# NewMUM_route2.net
KiCad netlist of a schematic drawn in EAGLE
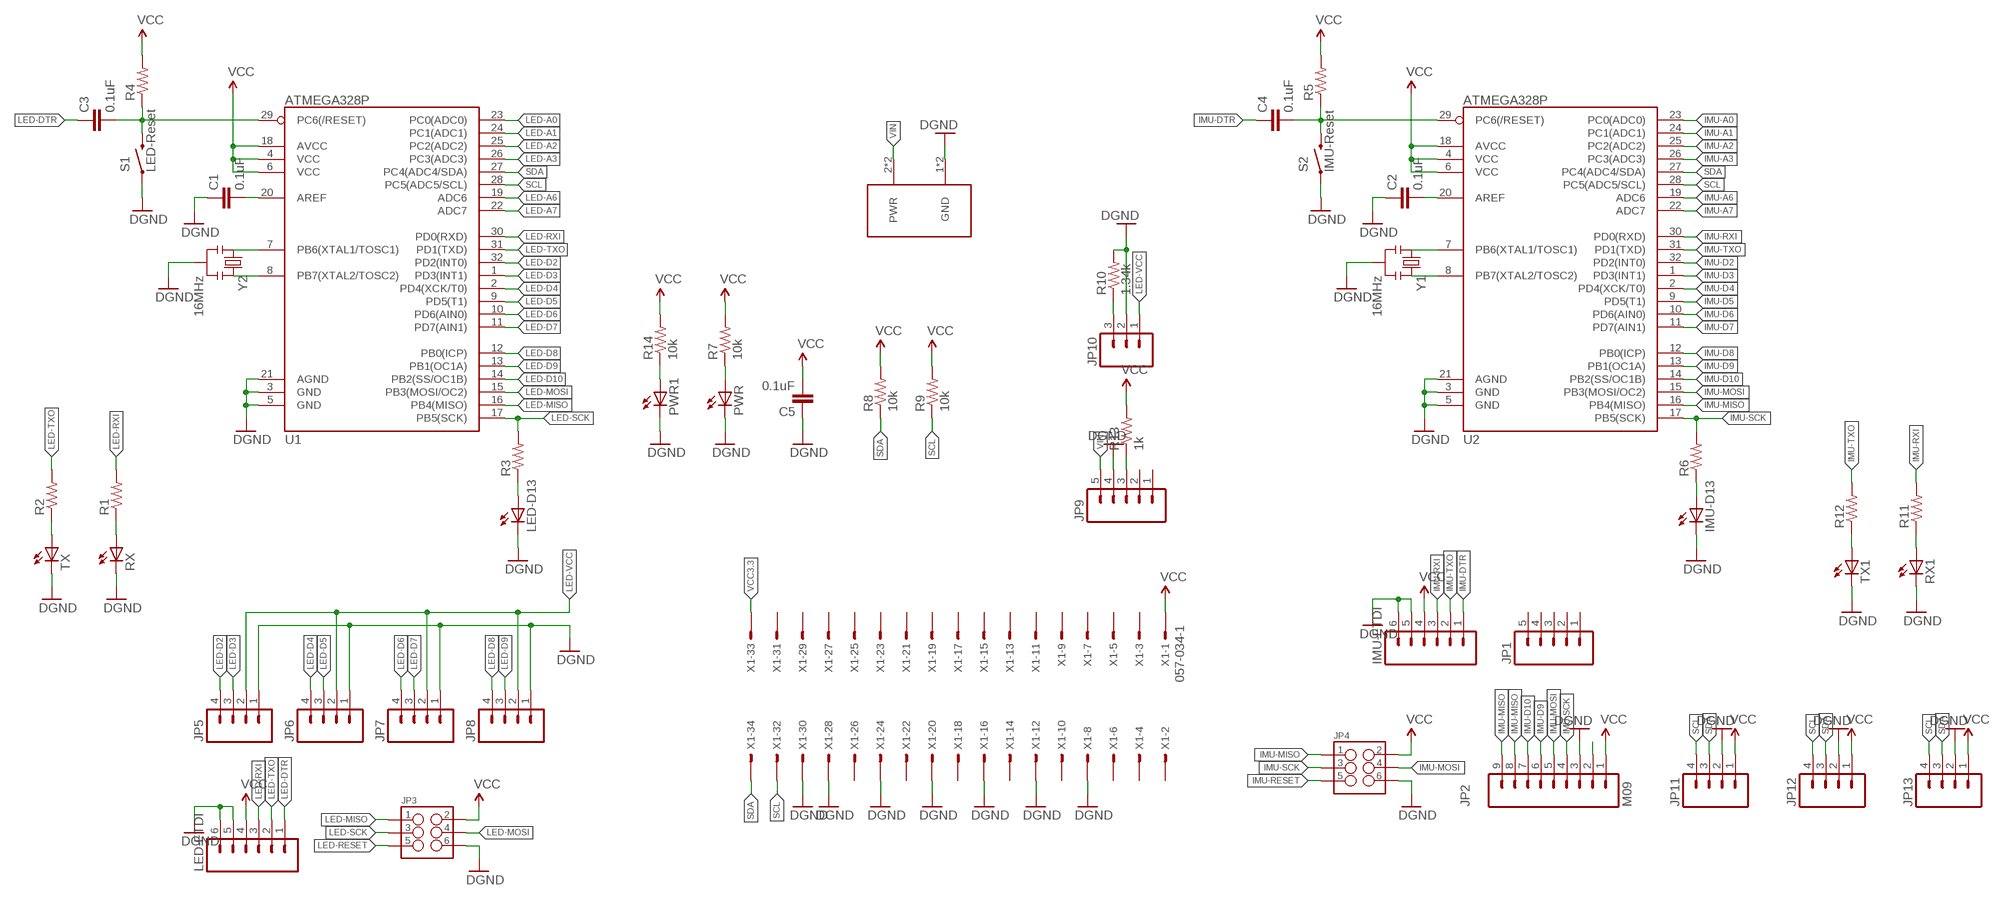
[diagram p0: schematic, sheet 1]

(export (version "E")
  (design (tool "Eeschema 10.0.6"))
  (components
    (comp (ref "C1")
      (value "0.1uF")
      (footprint "eagle-import:0805")
      (libsource (lib "eagle-import") (part "CAP0805"))
    )
    (comp (ref "C2")
      (value "0.1uF")
      (footprint "eagle-import:0805")
      (libsource (lib "eagle-import") (part "CAP0805"))
    )
    (comp (ref "C3")
      (value "0.1uF")
      (footprint "eagle-import:0805")
      (libsource (lib "eagle-import") (part "CAP0805"))
    )
    (comp (ref "C4")
      (value "0.1uF")
      (footprint "eagle-import:0805")
      (libsource (lib "eagle-import") (part "CAP0805"))
    )
    (comp (ref "C5")
      (value "0.1uF")
      (footprint "eagle-import:0805")
      (libsource (lib "eagle-import") (part "CAP0805"))
    )
    (comp (ref "IMU-D13")
      (value "LED1206")
      (footprint "eagle-import:LED-1206")
      (libsource (lib "eagle-import") (part "LED1206"))
    )
    (comp (ref "IMU-FTDI")
      (value "M06SIP")
      (footprint "eagle-import:1X06")
      (libsource (lib "eagle-import") (part "M06SIP"))
    )
    (comp (ref "JP1")
      (value "M05PTH")
      (footprint "eagle-import:1X05")
      (libsource (lib "eagle-import") (part "M05PTH"))
    )
    (comp (ref "JP2")
      (value "M09")
      (footprint "eagle-import:1X09")
      (libsource (lib "eagle-import") (part "M09"))
    )
    (comp (ref "JP3")
      (value "M03X22X3_SILK_SM")
      (footprint "eagle-import:2X3")
      (libsource (lib "eagle-import") (part "M03X22X3_SILK_SM"))
    )
    (comp (ref "JP4")
      (value "M03X22X3_SILK_SM")
      (footprint "eagle-import:2X3")
      (libsource (lib "eagle-import") (part "M03X22X3_SILK_SM"))
    )
    (comp (ref "JP5")
      (value "M04PTH")
      (footprint "eagle-import:1X04")
      (libsource (lib "eagle-import") (part "M04PTH"))
    )
    (comp (ref "JP6")
      (value "M04PTH")
      (footprint "eagle-import:1X04")
      (libsource (lib "eagle-import") (part "M04PTH"))
    )
    (comp (ref "JP7")
      (value "M04PTH")
      (footprint "eagle-import:1X04")
      (libsource (lib "eagle-import") (part "M04PTH"))
    )
    (comp (ref "JP8")
      (value "M04PTH")
      (footprint "eagle-import:1X04")
      (libsource (lib "eagle-import") (part "M04PTH"))
    )
    (comp (ref "JP9")
      (value "M05PTH")
      (footprint "eagle-import:1X05")
      (libsource (lib "eagle-import") (part "M05PTH"))
    )
    (comp (ref "JP10")
      (value "M03PTH")
      (footprint "eagle-import:1X03")
      (libsource (lib "eagle-import") (part "M03PTH"))
    )
    (comp (ref "JP11")
      (value "M04PTH")
      (footprint "eagle-import:1X04")
      (libsource (lib "eagle-import") (part "M04PTH"))
    )
    (comp (ref "JP12")
      (value "M04PTH")
      (footprint "eagle-import:1X04")
      (libsource (lib "eagle-import") (part "M04PTH"))
    )
    (comp (ref "JP13")
      (value "M04PTH")
      (footprint "eagle-import:1X04")
      (libsource (lib "eagle-import") (part "M04PTH"))
    )
    (comp (ref "LED-D13")
      (value "LED1206")
      (footprint "eagle-import:LED-1206")
      (libsource (lib "eagle-import") (part "LED1206"))
    )
    (comp (ref "LED-FTDI")
      (value "M06SIP")
      (footprint "eagle-import:1X06")
      (libsource (lib "eagle-import") (part "M06SIP"))
    )
    (comp (ref "PWR")
      (value "LED1206")
      (footprint "eagle-import:LED-1206")
      (libsource (lib "eagle-import") (part "LED1206"))
    )
    (comp (ref "PWR1")
      (value "LED1206")
      (footprint "eagle-import:LED-1206")
      (libsource (lib "eagle-import") (part "LED1206"))
    )
    (comp (ref "R1")
      (value "RESISTOR0805-RES")
      (footprint "eagle-import:0805")
      (libsource (lib "eagle-import") (part "RESISTOR0805-RES"))
    )
    (comp (ref "R2")
      (value "RESISTOR0805-RES")
      (footprint "eagle-import:0805")
      (libsource (lib "eagle-import") (part "RESISTOR0805-RES"))
    )
    (comp (ref "R3")
      (value "RESISTOR0805-RES")
      (footprint "eagle-import:0805")
      (libsource (lib "eagle-import") (part "RESISTOR0805-RES"))
    )
    (comp (ref "R4")
      (value "RESISTOR0805-RES")
      (footprint "eagle-import:0805")
      (libsource (lib "eagle-import") (part "RESISTOR0805-RES"))
    )
    (comp (ref "R5")
      (value "RESISTOR0805-RES")
      (footprint "eagle-import:0805")
      (libsource (lib "eagle-import") (part "RESISTOR0805-RES"))
    )
    (comp (ref "R6")
      (value "RESISTOR0805-RES")
      (footprint "eagle-import:0805")
      (libsource (lib "eagle-import") (part "RESISTOR0805-RES"))
    )
    (comp (ref "R7")
      (value "10k")
      (footprint "eagle-import:0805")
      (libsource (lib "eagle-import") (part "RESISTOR0805-RES"))
    )
    (comp (ref "R8")
      (value "10k")
      (footprint "eagle-import:0805")
      (libsource (lib "eagle-import") (part "RESISTOR0805-RES"))
    )
    (comp (ref "R9")
      (value "10k")
      (footprint "eagle-import:0805")
      (libsource (lib "eagle-import") (part "RESISTOR0805-RES"))
    )
    (comp (ref "R10")
      (value "1.34k")
      (footprint "eagle-import:AXIAL-0.3EZ")
      (libsource (lib "eagle-import") (part "RESISTOREZ"))
    )
    (comp (ref "R11")
      (value "RESISTOR0805-RES")
      (footprint "eagle-import:0805")
      (libsource (lib "eagle-import") (part "RESISTOR0805-RES"))
    )
    (comp (ref "R12")
      (value "RESISTOR0805-RES")
      (footprint "eagle-import:0805")
      (libsource (lib "eagle-import") (part "RESISTOR0805-RES"))
    )
    (comp (ref "R13")
      (value "1k")
      (footprint "eagle-import:0805")
      (libsource (lib "eagle-import") (part "RESISTOR0805-RES"))
    )
    (comp (ref "R14")
      (value "10k")
      (footprint "eagle-import:0805")
      (libsource (lib "eagle-import") (part "RESISTOR0805-RES"))
    )
    (comp (ref "RX")
      (value "LED1206")
      (footprint "eagle-import:LED-1206")
      (libsource (lib "eagle-import") (part "LED1206"))
    )
    (comp (ref "RX1")
      (value "LED1206")
      (footprint "eagle-import:LED-1206")
      (libsource (lib "eagle-import") (part "LED1206"))
    )
    (comp (ref "S1")
      (value "LED-Reset")
      (footprint "eagle-import:TACTILE-PTH")
      (libsource (lib "eagle-import") (part "SWITCH-MOMENTARY-2PTH"))
    )
    (comp (ref "S2")
      (value "IMU-Reset")
      (footprint "eagle-import:TACTILE-PTH")
      (libsource (lib "eagle-import") (part "SWITCH-MOMENTARY-2PTH"))
    )
    (comp (ref "TX")
      (value "LED1206")
      (footprint "eagle-import:LED-1206")
      (libsource (lib "eagle-import") (part "LED1206"))
    )
    (comp (ref "TX1")
      (value "LED1206")
      (footprint "eagle-import:LED-1206")
      (libsource (lib "eagle-import") (part "LED1206"))
    )
    (comp (ref "U$3")
      (value "LSF-SMT")
      (footprint "eagle-import:LSF-SMT")
      (libsource (lib "eagle-import") (part "LSF-SMT"))
    )
    (comp (ref "U1")
      (value "ATMEGA328P")
      (footprint "eagle-import:TQFP32-08")
      (libsource (lib "eagle-import") (part "ATMEGA328_SMT"))
    )
    (comp (ref "U2")
      (value "ATMEGA328P")
      (footprint "eagle-import:TQFP32-08")
      (libsource (lib "eagle-import") (part "ATMEGA328_SMT"))
    )
    (comp (ref "X1")
      (value "057-034-1")
      (footprint "eagle-import:057-034-1")
      (libsource (lib "eagle-import") (part "057-034-1"))
    )
    (comp (ref "Y1")
      (value "16MHz")
      (footprint "eagle-import:RESONATOR-SMD")
      (libsource (lib "eagle-import") (part "RESONATOR16MHZ"))
    )
    (comp (ref "Y2")
      (value "16MHz")
      (footprint "eagle-import:RESONATOR-SMD")
      (libsource (lib "eagle-import") (part "RESONATOR16MHZ"))
    )
  )
  (nets
    (net (code "1") (name "DGND") (class "Default")
      (node (ref "C1") (pin "1") (pinfunction "1_1") (pintype "passive"))
      (node (ref "C2") (pin "1") (pinfunction "1_1") (pintype "passive"))
      (node (ref "C5") (pin "1") (pinfunction "1_1") (pintype "passive"))
      (node (ref "IMU-D13") (pin "C") (pinfunction "C_C") (pintype "passive"))
      (node (ref "IMU-FTDI") (pin "5") (pinfunction "5_5") (pintype "passive"))
      (node (ref "IMU-FTDI") (pin "6") (pinfunction "6_6") (pintype "passive"))
      (node (ref "JP10") (pin "2") (pinfunction "2_2") (pintype "passive"))
      (node (ref "JP11") (pin "2") (pinfunction "2_2") (pintype "passive"))
      (node (ref "JP12") (pin "2") (pinfunction "2_2") (pintype "passive"))
      (node (ref "JP13") (pin "2") (pinfunction "2_2") (pintype "passive"))
      (node (ref "JP2") (pin "3") (pinfunction "3_3") (pintype "passive"))
      (node (ref "JP3") (pin "6") (pinfunction "6_6") (pintype "bidirectional"))
      (node (ref "JP4") (pin "6") (pinfunction "6_6") (pintype "bidirectional"))
      (node (ref "JP5") (pin "1") (pinfunction "1_1") (pintype "passive"))
      (node (ref "JP6") (pin "1") (pinfunction "1_1") (pintype "passive"))
      (node (ref "JP7") (pin "1") (pinfunction "1_1") (pintype "passive"))
      (node (ref "JP8") (pin "1") (pinfunction "1_1") (pintype "passive"))
      (node (ref "JP9") (pin "4") (pinfunction "4_4") (pintype "passive"))
      (node (ref "LED-D13") (pin "C") (pinfunction "C_C") (pintype "passive"))
      (node (ref "LED-FTDI") (pin "5") (pinfunction "5_5") (pintype "passive"))
      (node (ref "LED-FTDI") (pin "6") (pinfunction "6_6") (pintype "passive"))
      (node (ref "PWR") (pin "C") (pinfunction "C_C") (pintype "passive"))
      (node (ref "PWR1") (pin "C") (pinfunction "C_C") (pintype "passive"))
      (node (ref "R10") (pin "P$2") (pinfunction "2_P$2") (pintype "passive"))
      (node (ref "RX") (pin "C") (pinfunction "C_C") (pintype "passive"))
      (node (ref "RX1") (pin "C") (pinfunction "C_C") (pintype "passive"))
      (node (ref "S1") (pin "1") (pinfunction "1_1") (pintype "passive"))
      (node (ref "S2") (pin "1") (pinfunction "1_1") (pintype "passive"))
      (node (ref "TX") (pin "C") (pinfunction "C_C") (pintype "passive"))
      (node (ref "TX1") (pin "C") (pinfunction "C_C") (pintype "passive"))
      (node (ref "U$3") (pin "1") (pinfunction "GND_1") (pintype "bidirectional"))
      (node (ref "U$3") (pin "1-2") (pinfunction "GND_1-2") (pintype "bidirectional"))
      (node (ref "U1") (pin "21") (pinfunction "AGND_21") (pintype "bidirectional"))
      (node (ref "U1") (pin "3") (pinfunction "GND_3") (pintype "bidirectional"))
      (node (ref "U1") (pin "5") (pinfunction "GND_5") (pintype "bidirectional"))
      (node (ref "U2") (pin "21") (pinfunction "AGND_21") (pintype "bidirectional"))
      (node (ref "U2") (pin "3") (pinfunction "GND_3") (pintype "bidirectional"))
      (node (ref "U2") (pin "5") (pinfunction "GND_5") (pintype "bidirectional"))
      (node (ref "X1") (pin "12") (pinfunction "S_12") (pintype "passive"))
      (node (ref "X1") (pin "16") (pinfunction "S_16") (pintype "passive"))
      (node (ref "X1") (pin "20") (pinfunction "S_20") (pintype "passive"))
      (node (ref "X1") (pin "24") (pinfunction "S_24") (pintype "passive"))
      (node (ref "X1") (pin "28") (pinfunction "S_28") (pintype "passive"))
      (node (ref "X1") (pin "30") (pinfunction "S_30") (pintype "passive"))
      (node (ref "X1") (pin "8") (pinfunction "S_8") (pintype "passive"))
      (node (ref "Y1") (pin "2") (pinfunction "2_2") (pintype "passive"))
      (node (ref "Y2") (pin "2") (pinfunction "2_2") (pintype "passive"))
    )
    (net (code "2") (name "IMU-A0") (class "Default")
      (node (ref "U2") (pin "23") (pinfunction "PC0(ADC0)_23") (pintype "bidirectional"))
    )
    (net (code "3") (name "IMU-A1") (class "Default")
      (node (ref "U2") (pin "24") (pinfunction "PC1(ADC1)_24") (pintype "bidirectional"))
    )
    (net (code "4") (name "IMU-A2") (class "Default")
      (node (ref "U2") (pin "25") (pinfunction "PC2(ADC2)_25") (pintype "bidirectional"))
    )
    (net (code "5") (name "IMU-A3") (class "Default")
      (node (ref "U2") (pin "26") (pinfunction "PC3(ADC3)_26") (pintype "bidirectional"))
    )
    (net (code "6") (name "IMU-A6") (class "Default")
      (node (ref "U2") (pin "19") (pinfunction "ADC6_19") (pintype "bidirectional"))
    )
    (net (code "7") (name "IMU-A7") (class "Default")
      (node (ref "U2") (pin "22") (pinfunction "ADC7_22") (pintype "bidirectional"))
    )
    (net (code "8") (name "IMU-D2") (class "Default")
      (node (ref "U2") (pin "32") (pinfunction "PD2(INT0)_32") (pintype "bidirectional"))
    )
    (net (code "9") (name "IMU-D3") (class "Default")
      (node (ref "U2") (pin "1") (pinfunction "PD3(INT1)_1") (pintype "bidirectional"))
    )
    (net (code "10") (name "IMU-D4") (class "Default")
      (node (ref "U2") (pin "2") (pinfunction "PD4(XCK/T0)_2") (pintype "bidirectional"))
    )
    (net (code "11") (name "IMU-D5") (class "Default")
      (node (ref "U2") (pin "9") (pinfunction "PD5(T1)_9") (pintype "bidirectional"))
    )
    (net (code "12") (name "IMU-D6") (class "Default")
      (node (ref "U2") (pin "10") (pinfunction "PD6(AIN0)_10") (pintype "bidirectional"))
    )
    (net (code "13") (name "IMU-D7") (class "Default")
      (node (ref "U2") (pin "11") (pinfunction "PD7(AIN1)_11") (pintype "bidirectional"))
    )
    (net (code "14") (name "IMU-D8") (class "Default")
      (node (ref "U2") (pin "12") (pinfunction "PB0(ICP)_12") (pintype "bidirectional"))
    )
    (net (code "15") (name "IMU-D9") (class "Default")
      (node (ref "JP2") (pin "6") (pinfunction "6_6") (pintype "passive"))
      (node (ref "U2") (pin "13") (pinfunction "PB1(OC1A)_13") (pintype "bidirectional"))
    )
    (net (code "16") (name "IMU-D10") (class "Default")
      (node (ref "JP2") (pin "7") (pinfunction "7_7") (pintype "passive"))
      (node (ref "U2") (pin "14") (pinfunction "PB2(SS/OC1B)_14") (pintype "bidirectional"))
    )
    (net (code "17") (name "IMU-DTR") (class "Default")
      (node (ref "C4") (pin "1") (pinfunction "1_1") (pintype "passive"))
      (node (ref "IMU-FTDI") (pin "1") (pinfunction "1_1") (pintype "passive"))
    )
    (net (code "18") (name "IMU-MISO") (class "Default")
      (node (ref "JP2") (pin "8") (pinfunction "8_8") (pintype "passive"))
      (node (ref "JP2") (pin "9") (pinfunction "9_9") (pintype "passive"))
      (node (ref "JP4") (pin "1") (pinfunction "1_1") (pintype "bidirectional"))
      (node (ref "U2") (pin "16") (pinfunction "PB4(MISO)_16") (pintype "bidirectional"))
    )
    (net (code "19") (name "IMU-MOSI") (class "Default")
      (node (ref "JP2") (pin "5") (pinfunction "5_5") (pintype "passive"))
      (node (ref "JP4") (pin "4") (pinfunction "4_4") (pintype "bidirectional"))
      (node (ref "U2") (pin "15") (pinfunction "PB3(MOSI/OC2)_15") (pintype "bidirectional"))
    )
    (net (code "20") (name "IMU-RESET") (class "Default")
      (node (ref "C4") (pin "2") (pinfunction "2_2") (pintype "passive"))
      (node (ref "JP4") (pin "5") (pinfunction "5_5") (pintype "bidirectional"))
      (node (ref "R5") (pin "1") (pinfunction "1_1") (pintype "passive"))
      (node (ref "S2") (pin "3") (pinfunction "2_3") (pintype "passive"))
      (node (ref "U2") (pin "29") (pinfunction "PC6(/RESET)_29") (pintype "bidirectional"))
    )
    (net (code "21") (name "IMU-RXI") (class "Default")
      (node (ref "IMU-FTDI") (pin "3") (pinfunction "3_3") (pintype "passive"))
      (node (ref "R11") (pin "2") (pinfunction "2_2") (pintype "passive"))
      (node (ref "U2") (pin "30") (pinfunction "PD0(RXD)_30") (pintype "bidirectional"))
    )
    (net (code "22") (name "IMU-SCK") (class "Default")
      (node (ref "JP2") (pin "4") (pinfunction "4_4") (pintype "passive"))
      (node (ref "JP4") (pin "3") (pinfunction "3_3") (pintype "bidirectional"))
      (node (ref "R6") (pin "2") (pinfunction "2_2") (pintype "passive"))
      (node (ref "U2") (pin "17") (pinfunction "PB5(SCK)_17") (pintype "bidirectional"))
    )
    (net (code "23") (name "IMU-TXO") (class "Default")
      (node (ref "IMU-FTDI") (pin "2") (pinfunction "2_2") (pintype "passive"))
      (node (ref "R12") (pin "2") (pinfunction "2_2") (pintype "passive"))
      (node (ref "U2") (pin "31") (pinfunction "PD1(TXD)_31") (pintype "bidirectional"))
    )
    (net (code "24") (name "LED-A0") (class "Default")
      (node (ref "U1") (pin "23") (pinfunction "PC0(ADC0)_23") (pintype "bidirectional"))
    )
    (net (code "25") (name "LED-A1") (class "Default")
      (node (ref "U1") (pin "24") (pinfunction "PC1(ADC1)_24") (pintype "bidirectional"))
    )
    (net (code "26") (name "LED-A2") (class "Default")
      (node (ref "U1") (pin "25") (pinfunction "PC2(ADC2)_25") (pintype "bidirectional"))
    )
    (net (code "27") (name "LED-A3") (class "Default")
      (node (ref "U1") (pin "26") (pinfunction "PC3(ADC3)_26") (pintype "bidirectional"))
    )
    (net (code "28") (name "LED-A6") (class "Default")
      (node (ref "U1") (pin "19") (pinfunction "ADC6_19") (pintype "bidirectional"))
    )
    (net (code "29") (name "LED-A7") (class "Default")
      (node (ref "U1") (pin "22") (pinfunction "ADC7_22") (pintype "bidirectional"))
    )
    (net (code "30") (name "LED-D2") (class "Default")
      (node (ref "JP5") (pin "4") (pinfunction "4_4") (pintype "passive"))
      (node (ref "U1") (pin "32") (pinfunction "PD2(INT0)_32") (pintype "bidirectional"))
    )
    (net (code "31") (name "LED-D3") (class "Default")
      (node (ref "JP5") (pin "3") (pinfunction "3_3") (pintype "passive"))
      (node (ref "U1") (pin "1") (pinfunction "PD3(INT1)_1") (pintype "bidirectional"))
    )
    (net (code "32") (name "LED-D4") (class "Default")
      (node (ref "JP6") (pin "4") (pinfunction "4_4") (pintype "passive"))
      (node (ref "U1") (pin "2") (pinfunction "PD4(XCK/T0)_2") (pintype "bidirectional"))
    )
    (net (code "33") (name "LED-D5") (class "Default")
      (node (ref "JP6") (pin "3") (pinfunction "3_3") (pintype "passive"))
      (node (ref "U1") (pin "9") (pinfunction "PD5(T1)_9") (pintype "bidirectional"))
    )
    (net (code "34") (name "LED-D6") (class "Default")
      (node (ref "JP7") (pin "4") (pinfunction "4_4") (pintype "passive"))
      (node (ref "U1") (pin "10") (pinfunction "PD6(AIN0)_10") (pintype "bidirectional"))
    )
    (net (code "35") (name "LED-D7") (class "Default")
      (node (ref "JP7") (pin "3") (pinfunction "3_3") (pintype "passive"))
      (node (ref "U1") (pin "11") (pinfunction "PD7(AIN1)_11") (pintype "bidirectional"))
    )
    (net (code "36") (name "LED-D8") (class "Default")
      (node (ref "JP8") (pin "4") (pinfunction "4_4") (pintype "passive"))
      (node (ref "U1") (pin "12") (pinfunction "PB0(ICP)_12") (pintype "bidirectional"))
    )
    (net (code "37") (name "LED-D9") (class "Default")
      (node (ref "JP8") (pin "3") (pinfunction "3_3") (pintype "passive"))
      (node (ref "U1") (pin "13") (pinfunction "PB1(OC1A)_13") (pintype "bidirectional"))
    )
    (net (code "38") (name "LED-D10") (class "Default")
      (node (ref "U1") (pin "14") (pinfunction "PB2(SS/OC1B)_14") (pintype "bidirectional"))
    )
    (net (code "39") (name "LED-DTR") (class "Default")
      (node (ref "C3") (pin "1") (pinfunction "1_1") (pintype "passive"))
      (node (ref "LED-FTDI") (pin "1") (pinfunction "1_1") (pintype "passive"))
    )
    (net (code "40") (name "LED-MISO") (class "Default")
      (node (ref "JP3") (pin "1") (pinfunction "1_1") (pintype "bidirectional"))
      (node (ref "U1") (pin "16") (pinfunction "PB4(MISO)_16") (pintype "bidirectional"))
    )
    (net (code "41") (name "LED-MOSI") (class "Default")
      (node (ref "JP3") (pin "4") (pinfunction "4_4") (pintype "bidirectional"))
      (node (ref "U1") (pin "15") (pinfunction "PB3(MOSI/OC2)_15") (pintype "bidirectional"))
    )
    (net (code "42") (name "LED-RESET") (class "Default")
      (node (ref "C3") (pin "2") (pinfunction "2_2") (pintype "passive"))
      (node (ref "JP3") (pin "5") (pinfunction "5_5") (pintype "bidirectional"))
      (node (ref "R4") (pin "1") (pinfunction "1_1") (pintype "passive"))
      (node (ref "S1") (pin "3") (pinfunction "2_3") (pintype "passive"))
      (node (ref "U1") (pin "29") (pinfunction "PC6(/RESET)_29") (pintype "bidirectional"))
    )
    (net (code "43") (name "LED-RXI") (class "Default")
      (node (ref "LED-FTDI") (pin "3") (pinfunction "3_3") (pintype "passive"))
      (node (ref "R1") (pin "2") (pinfunction "2_2") (pintype "passive"))
      (node (ref "U1") (pin "30") (pinfunction "PD0(RXD)_30") (pintype "bidirectional"))
    )
    (net (code "44") (name "LED-SCK") (class "Default")
      (node (ref "JP3") (pin "3") (pinfunction "3_3") (pintype "bidirectional"))
      (node (ref "R3") (pin "2") (pinfunction "2_2") (pintype "passive"))
      (node (ref "U1") (pin "17") (pinfunction "PB5(SCK)_17") (pintype "bidirectional"))
    )
    (net (code "45") (name "LED-TXO") (class "Default")
      (node (ref "LED-FTDI") (pin "2") (pinfunction "2_2") (pintype "passive"))
      (node (ref "R2") (pin "2") (pinfunction "2_2") (pintype "passive"))
      (node (ref "U1") (pin "31") (pinfunction "PD1(TXD)_31") (pintype "bidirectional"))
    )
    (net (code "46") (name "LED-VCC") (class "Default")
      (node (ref "JP10") (pin "1") (pinfunction "1_1") (pintype "passive"))
      (node (ref "JP5") (pin "2") (pinfunction "2_2") (pintype "passive"))
      (node (ref "JP6") (pin "2") (pinfunction "2_2") (pintype "passive"))
      (node (ref "JP7") (pin "2") (pinfunction "2_2") (pintype "passive"))
      (node (ref "JP8") (pin "2") (pinfunction "2_2") (pintype "passive"))
    )
    (net (code "47") (name "Net-(IMU-D13-PadA)") (class "Default")
      (node (ref "IMU-D13") (pin "A") (pinfunction "A_A") (pintype "passive"))
      (node (ref "R6") (pin "1") (pinfunction "1_1") (pintype "passive"))
    )
    (net (code "48") (name "Net-(JP9-Pad3)") (class "Default")
      (node (ref "JP9") (pin "3") (pinfunction "3_3") (pintype "passive"))
      (node (ref "R13") (pin "1") (pinfunction "1_1") (pintype "passive"))
    )
    (net (code "49") (name "Net-(LED-D13-PadA)") (class "Default")
      (node (ref "LED-D13") (pin "A") (pinfunction "A_A") (pintype "passive"))
      (node (ref "R3") (pin "1") (pinfunction "1_1") (pintype "passive"))
    )
    (net (code "50") (name "Net-(PWR-PadA)") (class "Default")
      (node (ref "PWR") (pin "A") (pinfunction "A_A") (pintype "passive"))
      (node (ref "R7") (pin "1") (pinfunction "1_1") (pintype "passive"))
    )
    (net (code "51") (name "Net-(PWR1-PadA)") (class "Default")
      (node (ref "PWR1") (pin "A") (pinfunction "A_A") (pintype "passive"))
      (node (ref "R14") (pin "1") (pinfunction "1_1") (pintype "passive"))
    )
    (net (code "52") (name "Net-(R1-Pad1)") (class "Default")
      (node (ref "R1") (pin "1") (pinfunction "1_1") (pintype "passive"))
      (node (ref "RX") (pin "A") (pinfunction "A_A") (pintype "passive"))
    )
    (net (code "53") (name "Net-(R2-Pad1)") (class "Default")
      (node (ref "R2") (pin "1") (pinfunction "1_1") (pintype "passive"))
      (node (ref "TX") (pin "A") (pinfunction "A_A") (pintype "passive"))
    )
    (net (code "54") (name "Net-(R10-1)") (class "Default")
      (node (ref "JP10") (pin "3") (pinfunction "3_3") (pintype "passive"))
      (node (ref "R10") (pin "P$1") (pinfunction "1_P$1") (pintype "passive"))
    )
    (net (code "55") (name "Net-(R11-Pad1)") (class "Default")
      (node (ref "R11") (pin "1") (pinfunction "1_1") (pintype "passive"))
      (node (ref "RX1") (pin "A") (pinfunction "A_A") (pintype "passive"))
    )
    (net (code "56") (name "Net-(R12-Pad1)") (class "Default")
      (node (ref "R12") (pin "1") (pinfunction "1_1") (pintype "passive"))
      (node (ref "TX1") (pin "A") (pinfunction "A_A") (pintype "passive"))
    )
    (net (code "57") (name "Net-(U1-AREF)") (class "Default")
      (node (ref "C1") (pin "2") (pinfunction "2_2") (pintype "passive"))
      (node (ref "U1") (pin "20") (pinfunction "AREF_20") (pintype "bidirectional"))
    )
    (net (code "58") (name "Net-(U1-PB6(XTAL1{slash}TOSC1))") (class "Default")
      (node (ref "U1") (pin "7") (pinfunction "PB6(XTAL1/TOSC1)_7") (pintype "bidirectional"))
      (node (ref "Y2") (pin "1") (pinfunction "1_1") (pintype "passive"))
    )
    (net (code "59") (name "Net-(U1-PB7(XTAL2{slash}TOSC2))") (class "Default")
      (node (ref "U1") (pin "8") (pinfunction "PB7(XTAL2/TOSC2)_8") (pintype "bidirectional"))
      (node (ref "Y2") (pin "3") (pinfunction "3_3") (pintype "passive"))
    )
    (net (code "60") (name "Net-(U2-AREF)") (class "Default")
      (node (ref "C2") (pin "2") (pinfunction "2_2") (pintype "passive"))
      (node (ref "U2") (pin "20") (pinfunction "AREF_20") (pintype "bidirectional"))
    )
    (net (code "61") (name "Net-(U2-PB6(XTAL1{slash}TOSC1))") (class "Default")
      (node (ref "U2") (pin "7") (pinfunction "PB6(XTAL1/TOSC1)_7") (pintype "bidirectional"))
      (node (ref "Y1") (pin "1") (pinfunction "1_1") (pintype "passive"))
    )
    (net (code "62") (name "Net-(U2-PB7(XTAL2{slash}TOSC2))") (class "Default")
      (node (ref "U2") (pin "8") (pinfunction "PB7(XTAL2/TOSC2)_8") (pintype "bidirectional"))
      (node (ref "Y1") (pin "3") (pinfunction "3_3") (pintype "passive"))
    )
    (net (code "63") (name "SCL") (class "Default")
      (node (ref "JP11") (pin "4") (pinfunction "4_4") (pintype "passive"))
      (node (ref "JP12") (pin "4") (pinfunction "4_4") (pintype "passive"))
      (node (ref "JP13") (pin "4") (pinfunction "4_4") (pintype "passive"))
      (node (ref "R9") (pin "1") (pinfunction "1_1") (pintype "passive"))
      (node (ref "U1") (pin "28") (pinfunction "PC5(ADC5/SCL)_28") (pintype "bidirectional"))
      (node (ref "U2") (pin "28") (pinfunction "PC5(ADC5/SCL)_28") (pintype "bidirectional"))
      (node (ref "X1") (pin "32") (pinfunction "S_32") (pintype "passive"))
    )
    (net (code "64") (name "SDA") (class "Default")
      (node (ref "JP11") (pin "3") (pinfunction "3_3") (pintype "passive"))
      (node (ref "JP12") (pin "3") (pinfunction "3_3") (pintype "passive"))
      (node (ref "JP13") (pin "3") (pinfunction "3_3") (pintype "passive"))
      (node (ref "R8") (pin "1") (pinfunction "1_1") (pintype "passive"))
      (node (ref "U1") (pin "27") (pinfunction "PC4(ADC4/SDA)_27") (pintype "bidirectional"))
      (node (ref "U2") (pin "27") (pinfunction "PC4(ADC4/SDA)_27") (pintype "bidirectional"))
      (node (ref "X1") (pin "34") (pinfunction "S_34") (pintype "passive"))
    )
    (net (code "65") (name "VCC") (class "Default")
      (node (ref "C5") (pin "2") (pinfunction "2_2") (pintype "passive"))
      (node (ref "IMU-FTDI") (pin "4") (pinfunction "4_4") (pintype "passive"))
      (node (ref "JP11") (pin "1") (pinfunction "1_1") (pintype "passive"))
      (node (ref "JP12") (pin "1") (pinfunction "1_1") (pintype "passive"))
      (node (ref "JP13") (pin "1") (pinfunction "1_1") (pintype "passive"))
      (node (ref "JP2") (pin "1") (pinfunction "1_1") (pintype "passive"))
      (node (ref "JP3") (pin "2") (pinfunction "2_2") (pintype "bidirectional"))
      (node (ref "JP4") (pin "2") (pinfunction "2_2") (pintype "bidirectional"))
      (node (ref "LED-FTDI") (pin "4") (pinfunction "4_4") (pintype "passive"))
      (node (ref "R13") (pin "2") (pinfunction "2_2") (pintype "passive"))
      (node (ref "R14") (pin "2") (pinfunction "2_2") (pintype "passive"))
      (node (ref "R4") (pin "2") (pinfunction "2_2") (pintype "passive"))
      (node (ref "R5") (pin "2") (pinfunction "2_2") (pintype "passive"))
      (node (ref "R7") (pin "2") (pinfunction "2_2") (pintype "passive"))
      (node (ref "R8") (pin "2") (pinfunction "2_2") (pintype "passive"))
      (node (ref "R9") (pin "2") (pinfunction "2_2") (pintype "passive"))
      (node (ref "U1") (pin "18") (pinfunction "AVCC_18") (pintype "bidirectional"))
      (node (ref "U1") (pin "4") (pinfunction "VCC_4") (pintype "bidirectional"))
      (node (ref "U1") (pin "6") (pinfunction "VCC_6") (pintype "bidirectional"))
      (node (ref "U2") (pin "18") (pinfunction "AVCC_18") (pintype "bidirectional"))
      (node (ref "U2") (pin "4") (pinfunction "VCC_4") (pintype "bidirectional"))
      (node (ref "U2") (pin "6") (pinfunction "VCC_6") (pintype "bidirectional"))
      (node (ref "X1") (pin "1") (pinfunction "S_1") (pintype "passive"))
    )
    (net (code "66") (name "VCC3.3") (class "Default")
      (node (ref "X1") (pin "33") (pinfunction "S_33") (pintype "passive"))
    )
    (net (code "67") (name "VIN") (class "Default")
      (node (ref "JP9") (pin "5") (pinfunction "5_5") (pintype "passive"))
      (node (ref "U$3") (pin "2") (pinfunction "PWR_2") (pintype "bidirectional"))
      (node (ref "U$3") (pin "2-2") (pinfunction "PWR_2-2") (pintype "bidirectional"))
    )
    (net (code "68") (name "unconnected-(JP1-Pad1)") (class "Default")
      (node (ref "JP1") (pin "1") (pinfunction "1_1") (pintype "passive"))
    )
    (net (code "69") (name "unconnected-(JP1-Pad2)") (class "Default")
      (node (ref "JP1") (pin "2") (pinfunction "2_2") (pintype "passive"))
    )
    (net (code "70") (name "unconnected-(JP1-Pad3)") (class "Default")
      (node (ref "JP1") (pin "3") (pinfunction "3_3") (pintype "passive"))
    )
    (net (code "71") (name "unconnected-(JP1-Pad4)") (class "Default")
      (node (ref "JP1") (pin "4") (pinfunction "4_4") (pintype "passive"))
    )
    (net (code "72") (name "unconnected-(JP1-Pad5)") (class "Default")
      (node (ref "JP1") (pin "5") (pinfunction "5_5") (pintype "passive"))
    )
    (net (code "73") (name "unconnected-(JP2-Pad2)") (class "Default")
      (node (ref "JP2") (pin "2") (pinfunction "2_2") (pintype "passive"))
    )
    (net (code "74") (name "unconnected-(JP9-Pad1)") (class "Default")
      (node (ref "JP9") (pin "1") (pinfunction "1_1") (pintype "passive"))
    )
    (net (code "75") (name "unconnected-(JP9-Pad2)") (class "Default")
      (node (ref "JP9") (pin "2") (pinfunction "2_2") (pintype "passive"))
    )
    (net (code "76") (name "unconnected-(X1AC-S-Pad4)") (class "Default")
      (node (ref "X1") (pin "4") (pinfunction "S_4") (pintype "passive"))
    )
    (net (code "77") (name "unconnected-(X1AD-S-Pad5)") (class "Default")
      (node (ref "X1") (pin "5") (pinfunction "S_5") (pintype "passive"))
    )
    (net (code "78") (name "unconnected-(X1AE-S-Pad6)") (class "Default")
      (node (ref "X1") (pin "6") (pinfunction "S_6") (pintype "passive"))
    )
    (net (code "79") (name "unconnected-(X1AF-S-Pad7)") (class "Default")
      (node (ref "X1") (pin "7") (pinfunction "S_7") (pintype "passive"))
    )
    (net (code "80") (name "unconnected-(X1AH-S-Pad9)") (class "Default")
      (node (ref "X1") (pin "9") (pinfunction "S_9") (pintype "passive"))
    )
    (net (code "81") (name "unconnected-(X1B-S-Pad10)") (class "Default")
      (node (ref "X1") (pin "10") (pinfunction "S_10") (pintype "passive"))
    )
    (net (code "82") (name "unconnected-(X1C-S-Pad11)") (class "Default")
      (node (ref "X1") (pin "11") (pinfunction "S_11") (pintype "passive"))
    )
    (net (code "83") (name "unconnected-(X1E-S-Pad13)") (class "Default")
      (node (ref "X1") (pin "13") (pinfunction "S_13") (pintype "passive"))
    )
    (net (code "84") (name "unconnected-(X1F-S-Pad14)") (class "Default")
      (node (ref "X1") (pin "14") (pinfunction "S_14") (pintype "passive"))
    )
    (net (code "85") (name "unconnected-(X1G-S-Pad15)") (class "Default")
      (node (ref "X1") (pin "15") (pinfunction "S_15") (pintype "passive"))
    )
    (net (code "86") (name "unconnected-(X1I-S-Pad17)") (class "Default")
      (node (ref "X1") (pin "17") (pinfunction "S_17") (pintype "passive"))
    )
    (net (code "87") (name "unconnected-(X1J-S-Pad18)") (class "Default")
      (node (ref "X1") (pin "18") (pinfunction "S_18") (pintype "passive"))
    )
    (net (code "88") (name "unconnected-(X1K-S-Pad19)") (class "Default")
      (node (ref "X1") (pin "19") (pinfunction "S_19") (pintype "passive"))
    )
    (net (code "89") (name "unconnected-(X1L-S-Pad2)") (class "Default")
      (node (ref "X1") (pin "2") (pinfunction "S_2") (pintype "passive"))
    )
    (net (code "90") (name "unconnected-(X1N-S-Pad21)") (class "Default")
      (node (ref "X1") (pin "21") (pinfunction "S_21") (pintype "passive"))
    )
    (net (code "91") (name "unconnected-(X1O-S-Pad22)") (class "Default")
      (node (ref "X1") (pin "22") (pinfunction "S_22") (pintype "passive"))
    )
    (net (code "92") (name "unconnected-(X1P-S-Pad23)") (class "Default")
      (node (ref "X1") (pin "23") (pinfunction "S_23") (pintype "passive"))
    )
    (net (code "93") (name "unconnected-(X1R-S-Pad25)") (class "Default")
      (node (ref "X1") (pin "25") (pinfunction "S_25") (pintype "passive"))
    )
    (net (code "94") (name "unconnected-(X1S-S-Pad26)") (class "Default")
      (node (ref "X1") (pin "26") (pinfunction "S_26") (pintype "passive"))
    )
    (net (code "95") (name "unconnected-(X1T-S-Pad27)") (class "Default")
      (node (ref "X1") (pin "27") (pinfunction "S_27") (pintype "passive"))
    )
    (net (code "96") (name "unconnected-(X1V-S-Pad29)") (class "Default")
      (node (ref "X1") (pin "29") (pinfunction "S_29") (pintype "passive"))
    )
    (net (code "97") (name "unconnected-(X1W-S-Pad3)") (class "Default")
      (node (ref "X1") (pin "3") (pinfunction "S_3") (pintype "passive"))
    )
    (net (code "98") (name "unconnected-(X1Y-S-Pad31)") (class "Default")
      (node (ref "X1") (pin "31") (pinfunction "S_31") (pintype "passive"))
    )
  )
)
